# Esquema.net
KiCad netlist of a schematic drawn in EAGLE
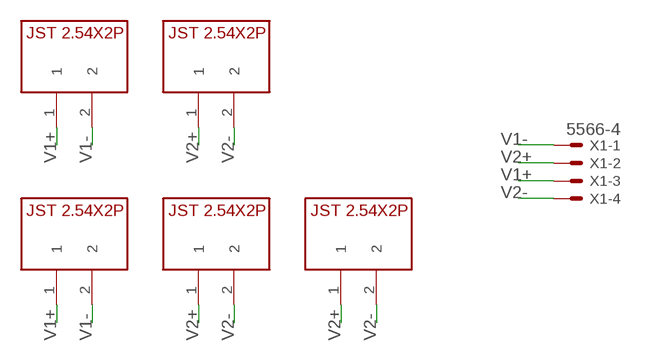
[diagram p0: schematic, sheet 1]

(export (version "E")
  (design (tool "Eeschema 10.0.6"))
  (components
    (comp (ref "U$1")
      (value "JST2.54X2P")
      (footprint "eagle-import:JST2.54X2P_FOOTPRINT")
      (libsource (lib "eagle-import") (part "JST2.54X2P"))
    )
    (comp (ref "U$2")
      (value "JST2.54X2P")
      (footprint "eagle-import:JST2.54X2P_FOOTPRINT")
      (libsource (lib "eagle-import") (part "JST2.54X2P"))
    )
    (comp (ref "U$3")
      (value "JST2.54X2P")
      (footprint "eagle-import:JST2.54X2P_FOOTPRINT")
      (libsource (lib "eagle-import") (part "JST2.54X2P"))
    )
    (comp (ref "U$4")
      (value "JST2.54X2P")
      (footprint "eagle-import:JST2.54X2P_FOOTPRINT")
      (libsource (lib "eagle-import") (part "JST2.54X2P"))
    )
    (comp (ref "U$5")
      (value "JST2.54X2P")
      (footprint "eagle-import:JST2.54X2P_FOOTPRINT")
      (libsource (lib "eagle-import") (part "JST2.54X2P"))
    )
    (comp (ref "X1")
      (value "5566-4")
      (footprint "eagle-import:5566-4")
      (fields (field (name "MF") "MOLEX"))
      (libsource (lib "eagle-import") (part "5566-4"))
    )
  )
  (nets
    (net (code "1") (name "/V1+") (class "Default")
      (node (ref "U$1") (pin "1") (pinfunction "1_1") (pintype "bidirectional"))
      (node (ref "U$4") (pin "1") (pinfunction "1_1") (pintype "bidirectional"))
      (node (ref "X1") (pin "3") (pinfunction "S_3") (pintype "passive"))
    )
    (net (code "2") (name "/V1-") (class "Default")
      (node (ref "U$1") (pin "2") (pinfunction "2_2") (pintype "bidirectional"))
      (node (ref "U$4") (pin "2") (pinfunction "2_2") (pintype "bidirectional"))
      (node (ref "X1") (pin "1") (pinfunction "S_1") (pintype "passive"))
    )
    (net (code "3") (name "/V2+") (class "Default")
      (node (ref "U$2") (pin "1") (pinfunction "1_1") (pintype "bidirectional"))
      (node (ref "U$3") (pin "1") (pinfunction "1_1") (pintype "bidirectional"))
      (node (ref "U$5") (pin "1") (pinfunction "1_1") (pintype "bidirectional"))
      (node (ref "X1") (pin "2") (pinfunction "S_2") (pintype "passive"))
    )
    (net (code "4") (name "/V2-") (class "Default")
      (node (ref "U$2") (pin "2") (pinfunction "2_2") (pintype "bidirectional"))
      (node (ref "U$3") (pin "2") (pinfunction "2_2") (pintype "bidirectional"))
      (node (ref "U$5") (pin "2") (pinfunction "2_2") (pintype "bidirectional"))
      (node (ref "X1") (pin "4") (pinfunction "S_4") (pintype "passive"))
    )
  )
)
